# 0-99_Counter.net
KiCad netlist of a schematic drawn in Altium Designer
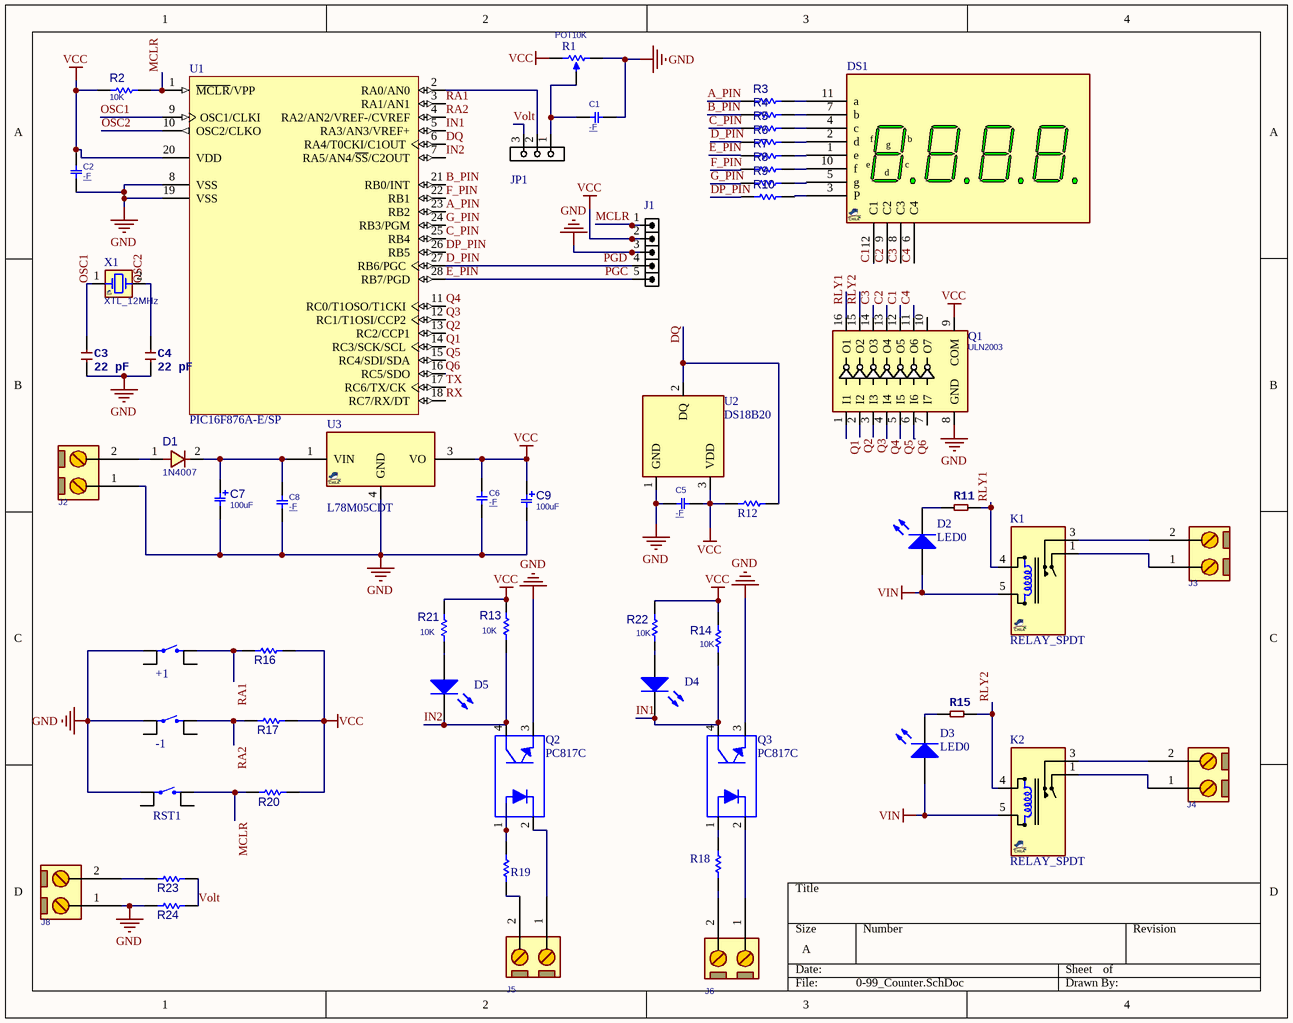
[diagram p0: 0-99_Counter.SchDoc]

(export (version "E")
  (design (tool "Eeschema 10.0.6"))
  (components
    (comp (ref "+1")
      (value "Tactile 4PIN 6X6mm H5mm (THD)")
      (footprint "SWPBT_SPDT_6X6X5SKHH")
      (description "Tactile Switch SPST-NO Top Actuated Surface Mount")
      (fields (field (name "PARTNUMBER") "PTS645SH50SMTR92 LFS"))
      (libsource (lib "Switch") (part "Tactile 4PIN 6X6mm H5mm (THD)"))
    )
    (comp (ref "-1")
      (value "Tactile 4PIN 6X6mm H5mm (THD)")
      (footprint "SWPBT_SPDT_6X6X5SKHH")
      (description "Tactile Switch SPST-NO Top Actuated Surface Mount")
      (fields (field (name "PARTNUMBER") "PTS645SH50SMTR92 LFS"))
      (libsource (lib "Switch") (part "Tactile 4PIN 6X6mm H5mm (THD)"))
    )
    (comp (ref "C1")
      (value "-F")
      (footprint "C0805")
      (description "CAP, MLCC, -F, -V, MATERIAL, -%, 0201")
      (fields (field (name "MANF_P#") "MANF_PART#"))
      (libsource (lib "all_lib") (part "CAP_SMD_MLCC_0805"))
    )
    (comp (ref "C2")
      (value "-F")
      (footprint "C0805")
      (description "CAP, MLCC, -F, -V, MATERIAL, -%, 0201")
      (fields (field (name "MANF_P#") "MANF_PART#"))
      (libsource (lib "all_lib") (part "CAP_SMD_MLCC_0805"))
    )
    (comp (ref "C3")
      (value "22 pF")
      (footprint "C0603")
      (fields (field (name "MPN") "GRM1885C1H102JA01D"))
      (libsource (lib "AltiumLibraryDDT") (part "CERAMIC-1NF-50V-5%-C0G(0603)"))
    )
    (comp (ref "C4")
      (value "22 pF")
      (footprint "C0603")
      (fields (field (name "MPN") "GRM1885C1H102JA01D"))
      (libsource (lib "AltiumLibraryDDT") (part "CERAMIC-1NF-50V-5%-C0G(0603)"))
    )
    (comp (ref "C5")
      (value "-F")
      (footprint "C0805")
      (description "CAP, MLCC, -F, -V, MATERIAL, -%, 0201")
      (fields (field (name "MANF_P#") "MANF_PART#"))
      (libsource (lib "all_lib") (part "CAP_SMD_MLCC_0805"))
    )
    (comp (ref "C6")
      (value "-F")
      (footprint "C0805")
      (description "CAP, MLCC, -F, -V, MATERIAL, -%, 0201")
      (fields (field (name "MANF_P#") "MANF_PART#"))
      (libsource (lib "all_lib") (part "CAP_SMD_MLCC_0805"))
    )
    (comp (ref "C7")
      (value "100uF")
      (footprint "C_EL_10X12")
      (description "CAP, THD, ELEC,")
      (fields (field (name "MANF_P#") "MANF_PART#") (field (name "MANF") "MANF"))
      (libsource (lib "all_lib") (part "CAP_THD_EL"))
    )
    (comp (ref "C8")
      (value "-F")
      (footprint "C0805")
      (description "CAP, MLCC, -F, -V, MATERIAL, -%, 0201")
      (fields (field (name "MANF_P#") "MANF_PART#"))
      (libsource (lib "all_lib") (part "CAP_SMD_MLCC_0805"))
    )
    (comp (ref "C9")
      (value "100uF")
      (footprint "C_EL_10X12")
      (description "CAP, THD, ELEC,")
      (fields (field (name "MANF_P#") "MANF_PART#") (field (name "MANF") "MANF"))
      (libsource (lib "all_lib") (part "CAP_THD_EL"))
    )
    (comp (ref "D1")
      (value "1N4007")
      (footprint "D_AX04_DO41")
      (description "DIODE, GENERAL PURPOSE, 1000V/1A")
      (fields (field (name "MANF") "Diodes"))
      (libsource (lib "all_lib") (part "DIODE_THD_1N4007"))
    )
    (comp (ref "D2")
      (value "LED0")
      (footprint "LED3MM")
      (description "Typical INFRARED GaAs LED")
      (fields (field (name "PUBLISHER") "Altium Limited"))
      (libsource (lib "Miscellaneous Devices") (part "LED0"))
    )
    (comp (ref "D3")
      (value "LED0")
      (footprint "LED3MM")
      (description "Typical INFRARED GaAs LED")
      (fields (field (name "PUBLISHER") "Altium Limited"))
      (libsource (lib "Miscellaneous Devices") (part "LED0"))
    )
    (comp (ref "D4")
      (value "LED1")
      (footprint "LED3MM")
      (description "Typical RED GaAs LED")
      (fields (field (name "PUBLISHER") "Altium Limited"))
      (libsource (lib "Miscellaneous Devices") (part "LED1"))
    )
    (comp (ref "D5")
      (value "LED1")
      (footprint "LED3MM")
      (description "Typical RED GaAs LED")
      (fields (field (name "PUBLISHER") "Altium Limited"))
      (libsource (lib "Miscellaneous Devices") (part "LED1"))
    )
    (comp (ref "DS1")
      (value "7SEG_4DIGIT_CC")
      (footprint "7SEGX4_12")
      (description "7SEGMENT, 4DIGIT, common cathode 5641")
      (fields (field (name "MANF_P#") "DPY-4CK"))
      (libsource (lib "all_lib") (part "7SEG_4DIGIT_CC"))
    )
    (comp (ref "J1")
      (value "HDR1X5")
      (footprint "HDR_M_1X5")
      (description "CONN, HEADER, Male, pitch: 2.54mm, 5POS")
      (libsource (lib "all_lib") (part "HDR_M_1X5"))
    )
    (comp (ref "J2")
      (value "CONN_TB2")
      (footprint "TBG_2")
      (description "CONN, TERMINAL BLOCK, 5.08mm pitch")
      (libsource (lib "") (part "CONN_TB2_1"))
    )
    (comp (ref "J3")
      (value "CONN_TB2")
      (footprint "TBG_2")
      (description "CONN, TERMINAL BLOCK, 5.08mm pitch")
      (libsource (lib "all_lib") (part "CONN_TB2"))
    )
    (comp (ref "J4")
      (value "CONN_TB2")
      (footprint "TBG_2")
      (description "CONN, TERMINAL BLOCK, 5.08mm pitch")
      (libsource (lib "all_lib") (part "CONN_TB2"))
    )
    (comp (ref "J5")
      (value "CONN_TB2")
      (footprint "TBG_2")
      (description "CONN, TERMINAL BLOCK, 5.08mm pitch")
      (libsource (lib "") (part "CONN_TB2_2"))
    )
    (comp (ref "J6")
      (value "CONN_TB2")
      (footprint "TBG_2")
      (description "CONN, TERMINAL BLOCK, 5.08mm pitch")
      (libsource (lib "") (part "CONN_TB2_2"))
    )
    (comp (ref "J8")
      (value "CONN_TB2")
      (footprint "TBG_2")
      (description "CONN, TERMINAL BLOCK, 5.08mm pitch")
      (libsource (lib "") (part "CONN_TB2_1"))
    )
    (comp (ref "JP1")
      (value "JMPHDR3PIN")
      (footprint "JP_3")
      (description "JUMPER, HEADER 3PIN")
      (fields (field (name "MANF") "MANF") (field (name "MANF_P#") "MANF_P#"))
      (libsource (lib "all_lib") (part "JUMPER_HDR_3P"))
    )
    (comp (ref "K1")
      (value "RELAY_SPDT")
      (footprint "REL_SPDT_5_2216")
      (description "Relay, SPDT, 5P, 22X16mm, 120V/10A")
      (fields (field (name "MANF") "OMRON") (field (name "MANF_P#") "G5LE-1"))
      (libsource (lib "all_lib") (part "RELAY_SPST_5_2216_G5LE"))
    )
    (comp (ref "K2")
      (value "RELAY_SPDT")
      (footprint "REL_SPDT_5_2216")
      (description "Relay, SPDT, 5P, 22X16mm, 120V/10A")
      (fields (field (name "MANF") "OMRON") (field (name "MANF_P#") "G5LE-1"))
      (libsource (lib "all_lib") (part "RELAY_SPST_5_2216_G5LE"))
    )
    (comp (ref "Q1")
      (value "ULN2003")
      (footprint "DIP_16")
      (description "Darlington, 7-CH, 50V, 0.5A, 6~15V CMOS/PMOS")
      (fields (field (name "MANF_P#") "ULN2004A") (field (name "MANF") "ST"))
      (libsource (lib "all_lib") (part "ULN2004_DIP16"))
    )
    (comp (ref "Q2")
      (value "PC817C")
      (footprint "DIP762W50P254L650H458Q4B")
      (description "Optoisolator Transistor Output 5000Vrms 1 Channel 4-DIP")
      (fields (field (name "MF") "Taiwan Semiconductor"))
      (libsource (lib "PC817C") (part "PC817C"))
    )
    (comp (ref "Q3")
      (value "PC817C")
      (footprint "DIP762W50P254L650H458Q4B")
      (description "Optoisolator Transistor Output 5000Vrms 1 Channel 4-DIP")
      (fields (field (name "MF") "Taiwan Semiconductor"))
      (libsource (lib "PC817C") (part "PC817C"))
    )
    (comp (ref "R1")
      (value "POT10K")
      (footprint "VOL_R")
      (description "RESISTOR, THD, Potentiometer Volume")
      (libsource (lib "all_lib") (part "RES_THD_POT_VOL"))
    )
    (comp (ref "R2")
      (value "10K")
      (footprint "R0805")
      (description "RESISTOR, THD")
      (fields (field (name "MANF_P#") "RK73H1ETTP4701F") (field (name "MANF") "KOA SPEER"))
      (libsource (lib "all_lib") (part "RES_THD"))
    )
    (comp (ref "R3")
      (value "10K")
      (footprint "R0805")
      (description "RESISTOR, THD")
      (fields (field (name "MANF_P#") "RK73H1ETTP4701F") (field (name "MANF") "KOA SPEER"))
      (libsource (lib "all_lib") (part "RES_THD"))
    )
    (comp (ref "R4")
      (value "10K")
      (footprint "R0805")
      (description "RESISTOR, THD")
      (fields (field (name "MANF_P#") "RK73H1ETTP4701F") (field (name "MANF") "KOA SPEER"))
      (libsource (lib "all_lib") (part "RES_THD"))
    )
    (comp (ref "R5")
      (value "10K")
      (footprint "R0805")
      (description "RESISTOR, THD")
      (fields (field (name "MANF_P#") "RK73H1ETTP4701F") (field (name "MANF") "KOA SPEER"))
      (libsource (lib "all_lib") (part "RES_THD"))
    )
    (comp (ref "R6")
      (value "10K")
      (footprint "R0805")
      (description "RESISTOR, THD")
      (fields (field (name "MANF_P#") "RK73H1ETTP4701F") (field (name "MANF") "KOA SPEER"))
      (libsource (lib "all_lib") (part "RES_THD"))
    )
    (comp (ref "R7")
      (value "10K")
      (footprint "R0805")
      (description "RESISTOR, THD")
      (fields (field (name "MANF_P#") "RK73H1ETTP4701F") (field (name "MANF") "KOA SPEER"))
      (libsource (lib "all_lib") (part "RES_THD"))
    )
    (comp (ref "R8")
      (value "10K")
      (footprint "R0805")
      (description "RESISTOR, THD")
      (fields (field (name "MANF_P#") "RK73H1ETTP4701F") (field (name "MANF") "KOA SPEER"))
      (libsource (lib "all_lib") (part "RES_THD"))
    )
    (comp (ref "R9")
      (value "10K")
      (footprint "R0805")
      (description "RESISTOR, THD")
      (fields (field (name "MANF_P#") "RK73H1ETTP4701F") (field (name "MANF") "KOA SPEER"))
      (libsource (lib "all_lib") (part "RES_THD"))
    )
    (comp (ref "R10")
      (value "10K")
      (footprint "R0805")
      (description "RESISTOR, THD")
      (fields (field (name "MANF_P#") "RK73H1ETTP4701F") (field (name "MANF") "KOA SPEER"))
      (libsource (lib "all_lib") (part "RES_THD"))
    )
    (comp (ref "R11") (value "~") (footprint "R0805") (libsource (lib "AltiumLibraryDDT") (part "RES_THT")))
    (comp (ref "R12")
      (value "10K")
      (footprint "R0805")
      (description "RESISTOR, THD 4K7")
      (fields (field (name "MANF_P#") "RK73H1ETTP4701F") (field (name "MANF") "KOA SPEER"))
      (libsource (lib "all_lib") (part "RES_THD"))
    )
    (comp (ref "R13")
      (value "10K")
      (footprint "R0805")
      (description "RESISTOR, THD")
      (fields (field (name "MANF_P#") "RK73H1ETTP4701F") (field (name "MANF") "KOA SPEER"))
      (libsource (lib "all_lib") (part "RES_THD"))
    )
    (comp (ref "R14")
      (value "10K")
      (footprint "R0805")
      (description "RESISTOR, THD")
      (fields (field (name "MANF_P#") "RK73H1ETTP4701F") (field (name "MANF") "KOA SPEER"))
      (libsource (lib "all_lib") (part "RES_THD"))
    )
    (comp (ref "R15") (value "~") (footprint "R0805") (libsource (lib "AltiumLibraryDDT") (part "RES_THT")))
    (comp (ref "R16")
      (value "10K")
      (footprint "R0805")
      (description "RESISTOR, THD 4K7")
      (fields (field (name "MANF_P#") "RK73H1ETTP4701F") (field (name "MANF") "KOA SPEER"))
      (libsource (lib "all_lib") (part "RES_THD"))
    )
    (comp (ref "R17")
      (value "10K")
      (footprint "R0805")
      (description "RESISTOR, THD")
      (fields (field (name "MANF_P#") "RK73H1ETTP4701F") (field (name "MANF") "KOA SPEER"))
      (libsource (lib "all_lib") (part "RES_THD"))
    )
    (comp (ref "R18")
      (value "10K")
      (footprint "R0805")
      (description "RESISTOR, THD 4K7")
      (fields (field (name "MANF_P#") "RK73H1ETTP4701F") (field (name "MANF") "KOA SPEER"))
      (libsource (lib "all_lib") (part "RES_THD"))
    )
    (comp (ref "R19")
      (value "10K")
      (footprint "R0805")
      (description "RESISTOR, THD 4K7")
      (fields (field (name "MANF_P#") "RK73H1ETTP4701F") (field (name "MANF") "KOA SPEER"))
      (libsource (lib "all_lib") (part "RES_THD"))
    )
    (comp (ref "R20")
      (value "10K")
      (footprint "R0805")
      (description "RESISTOR, THD")
      (fields (field (name "MANF_P#") "RK73H1ETTP4701F") (field (name "MANF") "KOA SPEER"))
      (libsource (lib "all_lib") (part "RES_THD"))
    )
    (comp (ref "R21")
      (value "10K")
      (footprint "R0805")
      (description "RESISTOR, THD")
      (fields (field (name "MANF_P#") "RK73H1ETTP4701F") (field (name "MANF") "KOA SPEER"))
      (libsource (lib "all_lib") (part "RES_THD"))
    )
    (comp (ref "R22")
      (value "10K")
      (footprint "R0805")
      (description "RESISTOR, THD")
      (fields (field (name "MANF_P#") "RK73H1ETTP4701F") (field (name "MANF") "KOA SPEER"))
      (libsource (lib "all_lib") (part "RES_THD"))
    )
    (comp (ref "R23")
      (value "10K")
      (footprint "R0805")
      (description "RESISTOR, THD")
      (fields (field (name "MANF_P#") "RK73H1ETTP4701F") (field (name "MANF") "KOA SPEER"))
      (libsource (lib "all_lib") (part "RES_THD"))
    )
    (comp (ref "R24")
      (value "10K")
      (footprint "R0805")
      (description "RESISTOR, THD")
      (fields (field (name "MANF_P#") "RK73H1ETTP4701F") (field (name "MANF") "KOA SPEER"))
      (libsource (lib "all_lib") (part "RES_THD"))
    )
    (comp (ref "RST1")
      (value "Tactile 4PIN 6X6mm H5mm (THD)")
      (footprint "SWPBT_SPDT_6X6X5SKHH")
      (description "Tactile Switch SPST-NO Top Actuated Surface Mount")
      (fields (field (name "PARTNUMBER") "PTS645SH50SMTR92 LFS"))
      (libsource (lib "Switch") (part "Tactile 4PIN 6X6mm H5mm (THD)"))
    )
    (comp (ref "U1")
      (value "PIC16F876A-E/SP")
      (footprint "SPDIP300-SP28")
      (fields (field (name "PUBLISHER") "Altium Limited"))
      (libsource (lib "Microchip Microcontroller 8-Bit PIC16") (part "PIC16F876A-E/SP"))
    )
    (comp (ref "U2")
      (value "DS18B20")
      (footprint "TO-92-TO92127P495H2044-3")
      (description "Temperature Sensor Digital, Local -55Â°C ~ 125Â°C 12 b TO-92-3")
      (fields (field (name "MF") "Maxim Integrated"))
      (libsource (lib "DS18B20") (part "DS18B20"))
    )
    (comp (ref "U3")
      (value "L78M05CDT")
      (footprint "DPAK_3")
      (description "REG, Linear, Fixed, 5v, 0.5A, TO-252")
      (fields (field (name "MANF") "TI, ST, FAIRCHILD, ON, NJR, ROHM, DIODES"))
      (libsource (lib "all_lib") (part "VREG_78M05_TO252"))
    )
    (comp (ref "X1")
      (value "XTL_12MHz")
      (footprint "XTLT_2")
      (description "Crystal MOST POPULAR ABL HC49 PACKAGE")
      (libsource (lib "all_lib") (part "XTL_2_HC49_SMD"))
    )
  )
  (nets
    (net (code "2") (name "/A_PIN") (class "Default")
      (node (ref "R3") (pin "1") (pinfunction "1_1") (pintype "passive"))
      (node (ref "U1") (pin "23") (pinfunction "RB2_23") (pintype "bidirectional"))
    )
    (net (code "3") (name "/B_PIN") (class "Default")
      (node (ref "R4") (pin "1") (pinfunction "1_1") (pintype "passive"))
      (node (ref "U1") (pin "21") (pinfunction "RB0/INT_21") (pintype "bidirectional"))
    )
    (net (code "4") (name "/C1") (class "Default")
      (node (ref "DS1") (pin "12") (pinfunction "C1_12") (pintype "passive"))
      (node (ref "Q1") (pin "12") (pinfunction "O5_12") (pintype "passive"))
    )
    (net (code "5") (name "/C2") (class "Default")
      (node (ref "DS1") (pin "9") (pinfunction "C2_9") (pintype "passive"))
      (node (ref "Q1") (pin "13") (pinfunction "O4_13") (pintype "passive"))
    )
    (net (code "6") (name "/C3") (class "Default")
      (node (ref "DS1") (pin "8") (pinfunction "C3_8") (pintype "passive"))
      (node (ref "Q1") (pin "14") (pinfunction "O3_14") (pintype "passive"))
    )
    (net (code "7") (name "/C4") (class "Default")
      (node (ref "DS1") (pin "6") (pinfunction "C4_6") (pintype "passive"))
      (node (ref "Q1") (pin "11") (pinfunction "O6_11") (pintype "passive"))
    )
    (net (code "8") (name "/C_PIN") (class "Default")
      (node (ref "R5") (pin "1") (pinfunction "1_1") (pintype "passive"))
      (node (ref "U1") (pin "25") (pinfunction "RB4_25") (pintype "bidirectional"))
    )
    (net (code "9") (name "/DP_PIN") (class "Default")
      (node (ref "R10") (pin "1") (pinfunction "1_1") (pintype "passive"))
      (node (ref "U1") (pin "26") (pinfunction "RB5_26") (pintype "bidirectional"))
    )
    (net (code "10") (name "/DQ") (class "Default")
      (node (ref "R12") (pin "1") (pinfunction "1_1") (pintype "passive"))
      (node (ref "U1") (pin "6") (pinfunction "RA4/T0CKI/C1OUT_6") (pintype "bidirectional"))
      (node (ref "U2") (pin "2") (pinfunction "DQ_2") (pintype "bidirectional"))
    )
    (net (code "11") (name "/D_PIN") (class "Default")
      (node (ref "J1") (pin "4") (pinfunction "4_4") (pintype "passive"))
      (node (ref "R6") (pin "1") (pinfunction "1_1") (pintype "passive"))
      (node (ref "U1") (pin "27") (pinfunction "RB6/PGC_27") (pintype "bidirectional"))
    )
    (net (code "12") (name "/E_PIN") (class "Default")
      (node (ref "J1") (pin "5") (pinfunction "5_5") (pintype "passive"))
      (node (ref "R7") (pin "1") (pinfunction "1_1") (pintype "passive"))
      (node (ref "U1") (pin "28") (pinfunction "RB7/PGD_28") (pintype "bidirectional"))
    )
    (net (code "13") (name "/F_PIN") (class "Default")
      (node (ref "R8") (pin "1") (pinfunction "1_1") (pintype "passive"))
      (node (ref "U1") (pin "22") (pinfunction "RB1_22") (pintype "bidirectional"))
    )
    (net (code "14") (name "/G_PIN") (class "Default")
      (node (ref "R9") (pin "1") (pinfunction "1_1") (pintype "passive"))
      (node (ref "U1") (pin "24") (pinfunction "RB3/PGM_24") (pintype "bidirectional"))
    )
    (net (code "15") (name "/IN1") (class "Default")
      (node (ref "D4") (pin "2") (pinfunction "K_2") (pintype "passive"))
      (node (ref "Q3") (pin "4") (pinfunction "4_4") (pintype "passive"))
      (node (ref "R14") (pin "1") (pinfunction "1_1") (pintype "passive"))
      (node (ref "U1") (pin "5") (pinfunction "RA3/AN3/VREF+_5") (pintype "bidirectional"))
    )
    (net (code "16") (name "/IN2") (class "Default")
      (node (ref "D5") (pin "2") (pinfunction "K_2") (pintype "passive"))
      (node (ref "Q2") (pin "4") (pinfunction "4_4") (pintype "passive"))
      (node (ref "R13") (pin "1") (pinfunction "1_1") (pintype "passive"))
      (node (ref "U1") (pin "7") (pinfunction "RA5/AN4/~{SS}/C2OUT_7") (pintype "bidirectional"))
    )
    (net (code "17") (name "/MCLR") (class "Default")
      (node (ref "J1") (pin "1") (pinfunction "1_1") (pintype "passive"))
      (node (ref "R2") (pin "2") (pinfunction "2_2") (pintype "passive"))
      (node (ref "R20") (pin "1") (pinfunction "1_1") (pintype "passive"))
      (node (ref "RST1") (pin "2") (pinfunction "2_2") (pintype "passive"))
      (node (ref "U1") (pin "1") (pinfunction "~{MCLR}/VPP_1") (pintype "input"))
    )
    (net (code "18") (name "/OSC1") (class "Default")
      (node (ref "C3") (pin "1") (pinfunction "1_1") (pintype "passive"))
      (node (ref "U1") (pin "9") (pinfunction "OSC1/CLKI_9") (pintype "input"))
      (node (ref "X1") (pin "1") (pinfunction "OSC1_1") (pintype "passive"))
    )
    (net (code "19") (name "/OSC2") (class "Default")
      (node (ref "C4") (pin "1") (pinfunction "1_1") (pintype "passive"))
      (node (ref "U1") (pin "10") (pinfunction "OSC2/CLKO_10") (pintype "output"))
      (node (ref "X1") (pin "2") (pinfunction "OSC2_2") (pintype "passive"))
    )
    (net (code "20") (name "/Q1") (class "Default")
      (node (ref "Q1") (pin "1") (pinfunction "I1_1") (pintype "passive"))
      (node (ref "U1") (pin "14") (pinfunction "RC3/SCK/SCL_14") (pintype "bidirectional"))
    )
    (net (code "21") (name "/Q2") (class "Default")
      (node (ref "Q1") (pin "2") (pinfunction "I2_2") (pintype "passive"))
      (node (ref "U1") (pin "13") (pinfunction "RC2/CCP1_13") (pintype "bidirectional"))
    )
    (net (code "22") (name "/Q3") (class "Default")
      (node (ref "Q1") (pin "3") (pinfunction "I3_3") (pintype "passive"))
      (node (ref "U1") (pin "12") (pinfunction "RC1/T1OSI/CCP2_12") (pintype "bidirectional"))
    )
    (net (code "23") (name "/Q4") (class "Default")
      (node (ref "Q1") (pin "4") (pinfunction "I4_4") (pintype "passive"))
      (node (ref "U1") (pin "11") (pinfunction "RC0/T1OSO/T1CKI_11") (pintype "bidirectional"))
    )
    (net (code "24") (name "/Q5") (class "Default")
      (node (ref "Q1") (pin "5") (pinfunction "I5_5") (pintype "passive"))
      (node (ref "U1") (pin "15") (pinfunction "RC4/SDI/SDA_15") (pintype "bidirectional"))
    )
    (net (code "25") (name "/Q6") (class "Default")
      (node (ref "Q1") (pin "6") (pinfunction "I6_6") (pintype "passive"))
      (node (ref "U1") (pin "16") (pinfunction "RC5/SDO_16") (pintype "bidirectional"))
    )
    (net (code "26") (name "/RA1") (class "Default")
      (node (ref "+1") (pin "2") (pinfunction "2_2") (pintype "passive"))
      (node (ref "R16") (pin "1") (pinfunction "1_1") (pintype "passive"))
      (node (ref "U1") (pin "3") (pinfunction "RA1/AN1_3") (pintype "bidirectional"))
    )
    (net (code "27") (name "/RA2") (class "Default")
      (node (ref "-1") (pin "2") (pinfunction "2_2") (pintype "passive"))
      (node (ref "R17") (pin "1") (pinfunction "1_1") (pintype "passive"))
      (node (ref "U1") (pin "4") (pinfunction "RA2/AN2/VREF-/CVREF_4") (pintype "bidirectional"))
    )
    (net (code "28") (name "/RLY1") (class "Default")
      (node (ref "K1") (pin "4") (pinfunction "T1_4") (pintype "passive"))
      (node (ref "Q1") (pin "16") (pinfunction "O1_16") (pintype "passive"))
      (node (ref "R11") (pin "2") (pinfunction "2_2") (pintype "passive"))
    )
    (net (code "29") (name "/RLY2") (class "Default")
      (node (ref "K2") (pin "4") (pinfunction "T1_4") (pintype "passive"))
      (node (ref "Q1") (pin "15") (pinfunction "O2_15") (pintype "passive"))
      (node (ref "R15") (pin "1") (pinfunction "1_1") (pintype "passive"))
    )
    (net (code "30") (name "/RX") (class "Default")
      (node (ref "U1") (pin "18") (pinfunction "RC7/RX/DT_18") (pintype "bidirectional"))
    )
    (net (code "31") (name "/TX") (class "Default")
      (node (ref "U1") (pin "17") (pinfunction "RC6/TX/CK_17") (pintype "bidirectional"))
    )
    (net (code "32") (name "/Volt") (class "Default")
      (node (ref "JP1") (pin "3") (pinfunction "3_3") (pintype "passive"))
      (node (ref "R23") (pin "1") (pinfunction "1_1") (pintype "passive"))
      (node (ref "R24") (pin "1") (pinfunction "1_1") (pintype "passive"))
    )
    (net (code "33") (name "GND") (class "Default")
      (node (ref "+1") (pin "1") (pinfunction "1_1") (pintype "passive"))
      (node (ref "-1") (pin "1") (pinfunction "1_1") (pintype "passive"))
      (node (ref "C1") (pin "2") (pinfunction "2_2") (pintype "passive"))
      (node (ref "C2") (pin "1") (pinfunction "1_1") (pintype "passive"))
      (node (ref "C3") (pin "2") (pinfunction "2_2") (pintype "passive"))
      (node (ref "C4") (pin "2") (pinfunction "2_2") (pintype "passive"))
      (node (ref "C5") (pin "2") (pinfunction "2_2") (pintype "passive"))
      (node (ref "C6") (pin "1") (pinfunction "1_1") (pintype "passive"))
      (node (ref "C7") (pin "2") (pinfunction "2_2") (pintype "passive"))
      (node (ref "C8") (pin "1") (pinfunction "1_1") (pintype "passive"))
      (node (ref "C9") (pin "2") (pinfunction "2_2") (pintype "passive"))
      (node (ref "J1") (pin "3") (pinfunction "3_3") (pintype "passive"))
      (node (ref "J2") (pin "1") (pinfunction "1_1") (pintype "passive"))
      (node (ref "J8") (pin "1") (pinfunction "1_1") (pintype "passive"))
      (node (ref "Q1") (pin "8") (pinfunction "GND_8") (pintype "passive"))
      (node (ref "Q2") (pin "3") (pinfunction "3_3") (pintype "passive"))
      (node (ref "Q3") (pin "3") (pinfunction "3_3") (pintype "passive"))
      (node (ref "R1") (pin "3") (pinfunction "BOT_3") (pintype "passive"))
      (node (ref "R24") (pin "2") (pinfunction "2_2") (pintype "passive"))
      (node (ref "RST1") (pin "1") (pinfunction "1_1") (pintype "passive"))
      (node (ref "U1") (pin "19") (pinfunction "VSS_19") (pintype "power_in"))
      (node (ref "U1") (pin "8") (pinfunction "VSS_8") (pintype "power_in"))
      (node (ref "U2") (pin "1") (pinfunction "GND_1") (pintype "power_in"))
      (node (ref "U3") (pin "4") (pinfunction "GND_4") (pintype "passive"))
    )
    (net (code "34") (name "Net-(D1-Pad1)") (class "Default")
      (node (ref "D1") (pin "1") (pinfunction "1_1") (pintype "passive"))
      (node (ref "J2") (pin "2") (pinfunction "2_2") (pintype "passive"))
    )
    (net (code "35") (name "Net-(D2-K)") (class "Default")
      (node (ref "D2") (pin "2") (pinfunction "K_2") (pintype "passive"))
      (node (ref "R11") (pin "1") (pinfunction "1_1") (pintype "passive"))
    )
    (net (code "36") (name "Net-(D3-K)") (class "Default")
      (node (ref "D3") (pin "2") (pinfunction "K_2") (pintype "passive"))
      (node (ref "R15") (pin "2") (pinfunction "2_2") (pintype "passive"))
    )
    (net (code "37") (name "Net-(D4-A)") (class "Default")
      (node (ref "D4") (pin "1") (pinfunction "A_1") (pintype "passive"))
      (node (ref "R22") (pin "1") (pinfunction "1_1") (pintype "passive"))
    )
    (net (code "38") (name "Net-(D5-A)") (class "Default")
      (node (ref "D5") (pin "1") (pinfunction "A_1") (pintype "passive"))
      (node (ref "R21") (pin "1") (pinfunction "1_1") (pintype "passive"))
    )
    (net (code "39") (name "Net-(DS1-P)") (class "Default")
      (node (ref "DS1") (pin "3") (pinfunction "P_3") (pintype "passive"))
      (node (ref "R10") (pin "2") (pinfunction "2_2") (pintype "passive"))
    )
    (net (code "40") (name "Net-(DS1-a)") (class "Default")
      (node (ref "DS1") (pin "11") (pinfunction "a_11") (pintype "passive"))
      (node (ref "R3") (pin "2") (pinfunction "2_2") (pintype "passive"))
    )
    (net (code "41") (name "Net-(DS1-b)") (class "Default")
      (node (ref "DS1") (pin "7") (pinfunction "b_7") (pintype "passive"))
      (node (ref "R4") (pin "2") (pinfunction "2_2") (pintype "passive"))
    )
    (net (code "42") (name "Net-(DS1-c)") (class "Default")
      (node (ref "DS1") (pin "4") (pinfunction "c_4") (pintype "passive"))
      (node (ref "R5") (pin "2") (pinfunction "2_2") (pintype "passive"))
    )
    (net (code "43") (name "Net-(DS1-d)") (class "Default")
      (node (ref "DS1") (pin "2") (pinfunction "d_2") (pintype "passive"))
      (node (ref "R6") (pin "2") (pinfunction "2_2") (pintype "passive"))
    )
    (net (code "44") (name "Net-(DS1-e)") (class "Default")
      (node (ref "DS1") (pin "1") (pinfunction "e_1") (pintype "passive"))
      (node (ref "R7") (pin "2") (pinfunction "2_2") (pintype "passive"))
    )
    (net (code "45") (name "Net-(DS1-f)") (class "Default")
      (node (ref "DS1") (pin "10") (pinfunction "f_10") (pintype "passive"))
      (node (ref "R8") (pin "2") (pinfunction "2_2") (pintype "passive"))
    )
    (net (code "46") (name "Net-(DS1-g)") (class "Default")
      (node (ref "DS1") (pin "5") (pinfunction "g_5") (pintype "passive"))
      (node (ref "R9") (pin "2") (pinfunction "2_2") (pintype "passive"))
    )
    (net (code "47") (name "Net-(J5-Pad1)") (class "Default")
      (node (ref "J5") (pin "1") (pinfunction "1_1") (pintype "passive"))
      (node (ref "Q2") (pin "2") (pinfunction "2_2") (pintype "passive"))
    )
    (net (code "48") (name "Net-(J5-Pad2)") (class "Default")
      (node (ref "J5") (pin "2") (pinfunction "2_2") (pintype "passive"))
      (node (ref "R19") (pin "2") (pinfunction "2_2") (pintype "passive"))
    )
    (net (code "49") (name "Net-(J6-Pad1)") (class "Default")
      (node (ref "J6") (pin "1") (pinfunction "1_1") (pintype "passive"))
      (node (ref "Q3") (pin "2") (pinfunction "2_2") (pintype "passive"))
    )
    (net (code "50") (name "Net-(J6-Pad2)") (class "Default")
      (node (ref "J6") (pin "2") (pinfunction "2_2") (pintype "passive"))
      (node (ref "R18") (pin "1") (pinfunction "1_1") (pintype "passive"))
    )
    (net (code "51") (name "Net-(J8-Pad2)") (class "Default")
      (node (ref "J8") (pin "2") (pinfunction "2_2") (pintype "passive"))
      (node (ref "R23") (pin "2") (pinfunction "2_2") (pintype "passive"))
    )
    (net (code "52") (name "Net-(K1-COM)") (class "Default")
      (node (ref "J3") (pin "1") (pinfunction "1_1") (pintype "passive"))
      (node (ref "K1") (pin "1") (pinfunction "COM_1") (pintype "passive"))
    )
    (net (code "53") (name "Net-(K1-NO)") (class "Default")
      (node (ref "J3") (pin "2") (pinfunction "2_2") (pintype "passive"))
      (node (ref "K1") (pin "3") (pinfunction "NO_3") (pintype "passive"))
    )
    (net (code "54") (name "Net-(K2-COM)") (class "Default")
      (node (ref "J4") (pin "1") (pinfunction "1_1") (pintype "passive"))
      (node (ref "K2") (pin "1") (pinfunction "COM_1") (pintype "passive"))
    )
    (net (code "55") (name "Net-(K2-NO)") (class "Default")
      (node (ref "J4") (pin "2") (pinfunction "2_2") (pintype "passive"))
      (node (ref "K2") (pin "3") (pinfunction "NO_3") (pintype "passive"))
    )
    (net (code "56") (name "Net-(Q2-Pad1)") (class "Default")
      (node (ref "Q2") (pin "1") (pinfunction "1_1") (pintype "passive"))
      (node (ref "R19") (pin "1") (pinfunction "1_1") (pintype "passive"))
    )
    (net (code "57") (name "Net-(Q3-Pad1)") (class "Default")
      (node (ref "Q3") (pin "1") (pinfunction "1_1") (pintype "passive"))
      (node (ref "R18") (pin "2") (pinfunction "2_2") (pintype "passive"))
    )
    (net (code "58") (name "Net-(R1-TAP)") (class "Default")
      (node (ref "C1") (pin "1") (pinfunction "1_1") (pintype "passive"))
      (node (ref "JP1") (pin "1") (pinfunction "1_1") (pintype "passive"))
      (node (ref "R1") (pin "2") (pinfunction "TAP_2") (pintype "passive"))
    )
    (net (code "59") (name "Net-(U1-RA0{slash}AN0)") (class "Default")
      (node (ref "JP1") (pin "2") (pinfunction "2_2") (pintype "passive"))
      (node (ref "U1") (pin "2") (pinfunction "RA0/AN0_2") (pintype "bidirectional"))
    )
    (net (code "60") (name "Net-(U3-VIN)") (class "Default")
      (node (ref "C7") (pin "1") (pinfunction "1_1") (pintype "passive"))
      (node (ref "C8") (pin "2") (pinfunction "2_2") (pintype "passive"))
      (node (ref "D1") (pin "2") (pinfunction "2_2") (pintype "passive"))
      (node (ref "U3") (pin "1") (pinfunction "VIN_1") (pintype "passive"))
    )
    (net (code "61") (name "VCC") (class "Default")
      (node (ref "C2") (pin "2") (pinfunction "2_2") (pintype "passive"))
      (node (ref "C5") (pin "1") (pinfunction "1_1") (pintype "passive"))
      (node (ref "C6") (pin "2") (pinfunction "2_2") (pintype "passive"))
      (node (ref "C9") (pin "1") (pinfunction "1_1") (pintype "passive"))
      (node (ref "J1") (pin "2") (pinfunction "2_2") (pintype "passive"))
      (node (ref "Q1") (pin "9") (pinfunction "COM_9") (pintype "passive"))
      (node (ref "R1") (pin "1") (pinfunction "TOP_1") (pintype "passive"))
      (node (ref "R12") (pin "2") (pinfunction "2_2") (pintype "passive"))
      (node (ref "R13") (pin "2") (pinfunction "2_2") (pintype "passive"))
      (node (ref "R14") (pin "2") (pinfunction "2_2") (pintype "passive"))
      (node (ref "R16") (pin "2") (pinfunction "2_2") (pintype "passive"))
      (node (ref "R17") (pin "2") (pinfunction "2_2") (pintype "passive"))
      (node (ref "R2") (pin "1") (pinfunction "1_1") (pintype "passive"))
      (node (ref "R20") (pin "2") (pinfunction "2_2") (pintype "passive"))
      (node (ref "R21") (pin "2") (pinfunction "2_2") (pintype "passive"))
      (node (ref "R22") (pin "2") (pinfunction "2_2") (pintype "passive"))
      (node (ref "U1") (pin "20") (pinfunction "VDD_20") (pintype "power_in"))
      (node (ref "U2") (pin "3") (pinfunction "VDD_3") (pintype "power_in"))
      (node (ref "U3") (pin "3") (pinfunction "VO_3") (pintype "passive"))
    )
    (net (code "62") (name "VIN") (class "Default")
      (node (ref "D2") (pin "1") (pinfunction "A_1") (pintype "passive"))
      (node (ref "D3") (pin "1") (pinfunction "A_1") (pintype "passive"))
      (node (ref "K1") (pin "5") (pinfunction "T2_5") (pintype "passive"))
      (node (ref "K2") (pin "5") (pinfunction "T2_5") (pintype "passive"))
    )
    (net (code "63") (name "unconnected-(+1-Pad3)") (class "Default")
      (node (ref "+1") (pin "3") (pinfunction "3_3") (pintype "passive"))
    )
    (net (code "64") (name "unconnected-(+1-Pad4)") (class "Default")
      (node (ref "+1") (pin "4") (pinfunction "4_4") (pintype "passive"))
    )
    (net (code "65") (name "unconnected-(-1-Pad3)") (class "Default")
      (node (ref "-1") (pin "3") (pinfunction "3_3") (pintype "passive"))
    )
    (net (code "66") (name "unconnected-(-1-Pad4)") (class "Default")
      (node (ref "-1") (pin "4") (pinfunction "4_4") (pintype "passive"))
    )
    (net (code "67") (name "unconnected-(Q1-I7-Pad7)") (class "Default")
      (node (ref "Q1") (pin "7") (pinfunction "I7_7") (pintype "passive"))
    )
    (net (code "68") (name "unconnected-(Q1-O7-Pad10)") (class "Default")
      (node (ref "Q1") (pin "10") (pinfunction "O7_10") (pintype "passive"))
    )
    (net (code "69") (name "unconnected-(RST1-Pad3)") (class "Default")
      (node (ref "RST1") (pin "3") (pinfunction "3_3") (pintype "passive"))
    )
    (net (code "70") (name "unconnected-(RST1-Pad4)") (class "Default")
      (node (ref "RST1") (pin "4") (pinfunction "4_4") (pintype "passive"))
    )
  )
)
